# Pwr.net
KiCad netlist of a schematic drawn in Altium Designer
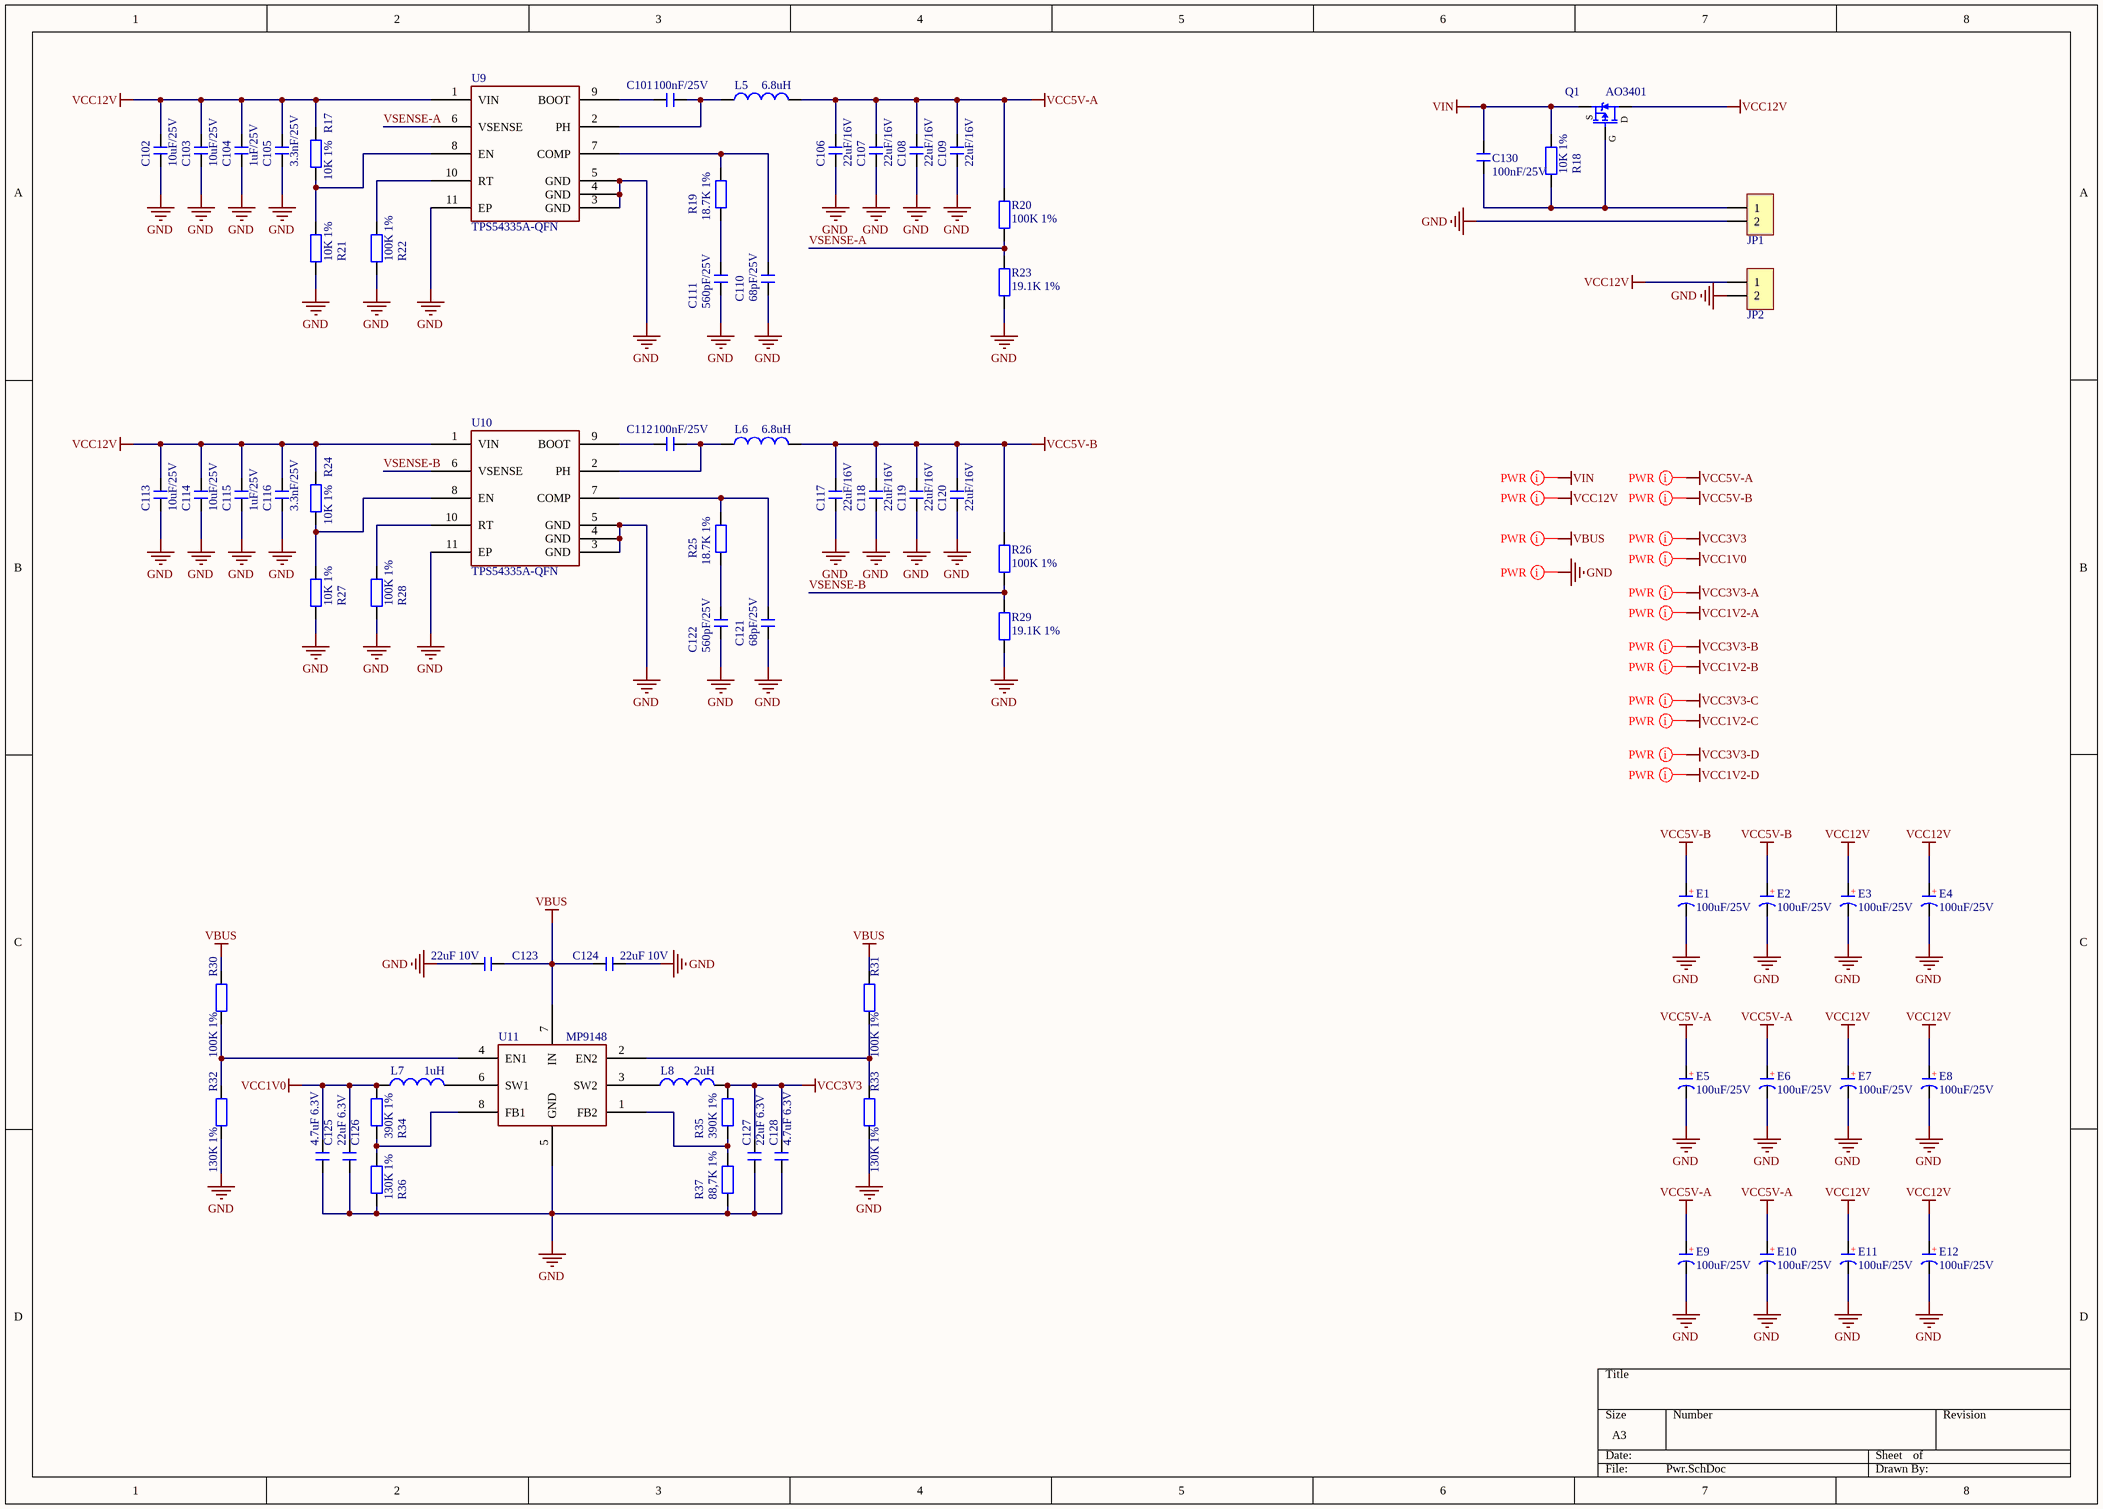
[diagram p0: Pwr.SchDoc]

(export (version "E")
  (design (tool "Eeschema 10.0.6"))
  (components
    (comp (ref "C101")
      (value "100nF/25V")
      (footprint "C0402_L")
      (description "无极性贴片电容")
      (fields (field (name "版权归属") "源创客"))
      (libsource (lib "Capacitor") (part "C"))
    )
    (comp (ref "C102")
      (value "10uF/25V")
      (footprint "C0603_L")
      (description "无极性贴片电容")
      (fields (field (name "版权归属") "源创客"))
      (libsource (lib "Capacitor") (part "C"))
    )
    (comp (ref "C103")
      (value "10uF/25V")
      (footprint "C0603_L")
      (description "无极性贴片电容")
      (fields (field (name "版权归属") "源创客"))
      (libsource (lib "Capacitor") (part "C"))
    )
    (comp (ref "C104")
      (value "1uF/25V")
      (footprint "C0603_L")
      (description "无极性贴片电容")
      (fields (field (name "版权归属") "源创客"))
      (libsource (lib "Capacitor") (part "C"))
    )
    (comp (ref "C105")
      (value "3.3nF/25V")
      (footprint "C0603_L")
      (description "无极性贴片电容")
      (fields (field (name "版权归属") "源创客"))
      (libsource (lib "Capacitor") (part "C"))
    )
    (comp (ref "C106")
      (value "22uF/16V")
      (footprint "C0603_L")
      (description "无极性贴片电容")
      (fields (field (name "版权归属") "源创客"))
      (libsource (lib "Capacitor") (part "C"))
    )
    (comp (ref "C107")
      (value "22uF/16V")
      (footprint "C0603_L")
      (description "无极性贴片电容")
      (fields (field (name "版权归属") "源创客"))
      (libsource (lib "Capacitor") (part "C"))
    )
    (comp (ref "C108")
      (value "22uF/16V")
      (footprint "C0603_L")
      (description "无极性贴片电容")
      (fields (field (name "版权归属") "源创客"))
      (libsource (lib "Capacitor") (part "C"))
    )
    (comp (ref "C109")
      (value "22uF/16V")
      (footprint "C0603_L")
      (description "无极性贴片电容")
      (fields (field (name "版权归属") "源创客"))
      (libsource (lib "Capacitor") (part "C"))
    )
    (comp (ref "C110")
      (value "68pF/25V")
      (footprint "C0402_L")
      (description "无极性贴片电容")
      (fields (field (name "版权归属") "源创客"))
      (libsource (lib "Capacitor") (part "C"))
    )
    (comp (ref "C111")
      (value "560pF/25V")
      (footprint "C0402_L")
      (description "无极性贴片电容")
      (fields (field (name "版权归属") "源创客"))
      (libsource (lib "Capacitor") (part "C"))
    )
    (comp (ref "C112")
      (value "100nF/25V")
      (footprint "C0402_L")
      (description "无极性贴片电容")
      (fields (field (name "版权归属") "源创客"))
      (libsource (lib "Capacitor") (part "C"))
    )
    (comp (ref "C113")
      (value "10uF/25V")
      (footprint "C0603_L")
      (description "无极性贴片电容")
      (fields (field (name "版权归属") "源创客"))
      (libsource (lib "Capacitor") (part "C"))
    )
    (comp (ref "C114")
      (value "10uF/25V")
      (footprint "C0603_L")
      (description "无极性贴片电容")
      (fields (field (name "版权归属") "源创客"))
      (libsource (lib "Capacitor") (part "C"))
    )
    (comp (ref "C115")
      (value "1uF/25V")
      (footprint "C0603_L")
      (description "无极性贴片电容")
      (fields (field (name "版权归属") "源创客"))
      (libsource (lib "Capacitor") (part "C"))
    )
    (comp (ref "C116")
      (value "3.3nF/25V")
      (footprint "C0603_L")
      (description "无极性贴片电容")
      (fields (field (name "版权归属") "源创客"))
      (libsource (lib "Capacitor") (part "C"))
    )
    (comp (ref "C117")
      (value "22uF/16V")
      (footprint "C0603_L")
      (description "无极性贴片电容")
      (fields (field (name "版权归属") "源创客"))
      (libsource (lib "Capacitor") (part "C"))
    )
    (comp (ref "C118")
      (value "22uF/16V")
      (footprint "C0603_L")
      (description "无极性贴片电容")
      (fields (field (name "版权归属") "源创客"))
      (libsource (lib "Capacitor") (part "C"))
    )
    (comp (ref "C119")
      (value "22uF/16V")
      (footprint "C0603_L")
      (description "无极性贴片电容")
      (fields (field (name "版权归属") "源创客"))
      (libsource (lib "Capacitor") (part "C"))
    )
    (comp (ref "C120")
      (value "22uF/16V")
      (footprint "C0603_L")
      (description "无极性贴片电容")
      (fields (field (name "版权归属") "源创客"))
      (libsource (lib "Capacitor") (part "C"))
    )
    (comp (ref "C121")
      (value "68pF/25V")
      (footprint "C0402_L")
      (description "无极性贴片电容")
      (fields (field (name "版权归属") "源创客"))
      (libsource (lib "Capacitor") (part "C"))
    )
    (comp (ref "C122")
      (value "560pF/25V")
      (footprint "C0402_L")
      (description "无极性贴片电容")
      (fields (field (name "版权归属") "源创客"))
      (libsource (lib "Capacitor") (part "C"))
    )
    (comp (ref "C123")
      (value "22uF 10V")
      (footprint "C0603_L")
      (description "无极性贴片电容")
      (fields (field (name "版权归属") "源创客"))
      (libsource (lib "Capacitor") (part "C"))
    )
    (comp (ref "C124")
      (value "22uF 10V")
      (footprint "C0603_L")
      (description "无极性贴片电容")
      (fields (field (name "版权归属") "源创客"))
      (libsource (lib "Capacitor") (part "C"))
    )
    (comp (ref "C125")
      (value "4.7uF 6.3V")
      (footprint "C0603_L")
      (description "无极性贴片电容")
      (fields (field (name "版权归属") "源创客"))
      (libsource (lib "Capacitor") (part "C"))
    )
    (comp (ref "C126")
      (value "22uF 6.3V")
      (footprint "C0603_L")
      (description "无极性贴片电容")
      (fields (field (name "版权归属") "源创客"))
      (libsource (lib "Capacitor") (part "C"))
    )
    (comp (ref "C127")
      (value "22uF 6.3V")
      (footprint "C0603_L")
      (description "无极性贴片电容")
      (fields (field (name "版权归属") "源创客"))
      (libsource (lib "Capacitor") (part "C"))
    )
    (comp (ref "C128")
      (value "4.7uF 6.3V")
      (footprint "C0603_L")
      (description "无极性贴片电容")
      (fields (field (name "版权归属") "源创客"))
      (libsource (lib "Capacitor") (part "C"))
    )
    (comp (ref "C130")
      (value "100nF/25V")
      (footprint "C0402_L")
      (description "无极性贴片电容")
      (fields (field (name "版权归属") "源创客"))
      (libsource (lib "Capacitor") (part "C"))
    )
    (comp (ref "E1")
      (value "100uF/25V")
      (footprint "CS 6*4 - B")
      (description "贴片钽电容")
      (fields (field (name "版权归属") "源创客"))
      (libsource (lib "Capacitor") (part "C-CD"))
    )
    (comp (ref "E2")
      (value "100uF/25V")
      (footprint "CS 6*4 - B")
      (description "贴片钽电容")
      (fields (field (name "版权归属") "源创客"))
      (libsource (lib "Capacitor") (part "C-CD"))
    )
    (comp (ref "E3")
      (value "100uF/25V")
      (footprint "CS 6*4 - B")
      (description "贴片钽电容")
      (fields (field (name "版权归属") "源创客"))
      (libsource (lib "Capacitor") (part "C-CD"))
    )
    (comp (ref "E4")
      (value "100uF/25V")
      (footprint "CS 6*4 - B")
      (description "贴片钽电容")
      (fields (field (name "版权归属") "源创客"))
      (libsource (lib "Capacitor") (part "C-CD"))
    )
    (comp (ref "E5")
      (value "100uF/25V")
      (footprint "CS 6*4 - B")
      (description "贴片钽电容")
      (fields (field (name "版权归属") "源创客"))
      (libsource (lib "Capacitor") (part "C-CD"))
    )
    (comp (ref "E6")
      (value "100uF/25V")
      (footprint "CS 6*4 - B")
      (description "贴片钽电容")
      (fields (field (name "版权归属") "源创客"))
      (libsource (lib "Capacitor") (part "C-CD"))
    )
    (comp (ref "E7")
      (value "100uF/25V")
      (footprint "CS 6*4 - B")
      (description "贴片钽电容")
      (fields (field (name "版权归属") "源创客"))
      (libsource (lib "Capacitor") (part "C-CD"))
    )
    (comp (ref "E8")
      (value "100uF/25V")
      (footprint "CS 6*4 - B")
      (description "贴片钽电容")
      (fields (field (name "版权归属") "源创客"))
      (libsource (lib "Capacitor") (part "C-CD"))
    )
    (comp (ref "E9")
      (value "100uF/25V")
      (footprint "CS 6*4 - B")
      (description "贴片钽电容")
      (fields (field (name "版权归属") "源创客"))
      (libsource (lib "Capacitor") (part "C-CD"))
    )
    (comp (ref "E10")
      (value "100uF/25V")
      (footprint "CS 6*4 - B")
      (description "贴片钽电容")
      (fields (field (name "版权归属") "源创客"))
      (libsource (lib "Capacitor") (part "C-CD"))
    )
    (comp (ref "E11")
      (value "100uF/25V")
      (footprint "CS 6*4 - B")
      (description "贴片钽电容")
      (fields (field (name "版权归属") "源创客"))
      (libsource (lib "Capacitor") (part "C-CD"))
    )
    (comp (ref "E12")
      (value "100uF/25V")
      (footprint "CS 6*4 - B")
      (description "贴片钽电容")
      (fields (field (name "版权归属") "源创客"))
      (libsource (lib "Capacitor") (part "C-CD"))
    )
    (comp (ref "JP1")
      (value "HDR-1X2")
      (footprint "ZH1.5-WS-2P")
      (description "2P接插件")
      (fields (field (name "版权归属") "源创客"))
      (libsource (lib "Connector-PinHeader") (part "Header 2"))
    )
    (comp (ref "JP2")
      (value "HDR-1X2")
      (footprint "XH2.54-WS-2P")
      (description "2P接插件")
      (fields (field (name "版权归属") "源创客"))
      (libsource (lib "Connector-PinHeader") (part "Header 2"))
    )
    (comp (ref "L5")
      (value "6.8uH")
      (footprint "NR4020")
      (description "小功率贴片电感")
      (fields (field (name "版权归属") "源创客"))
      (libsource (lib "Inductor") (part "L"))
    )
    (comp (ref "L6")
      (value "6.8uH")
      (footprint "NR4020")
      (description "小功率贴片电感")
      (fields (field (name "版权归属") "源创客"))
      (libsource (lib "Inductor") (part "L"))
    )
    (comp (ref "L7")
      (value "1uH")
      (footprint "NR4020")
      (description "小功率贴片电感")
      (fields (field (name "版权归属") "源创客"))
      (libsource (lib "Inductor") (part "L"))
    )
    (comp (ref "L8")
      (value "2uH")
      (footprint "NR4020")
      (description "小功率贴片电感")
      (fields (field (name "版权归属") "源创客"))
      (libsource (lib "") (part "L_1"))
    )
    (comp (ref "Q1")
      (value "AO3401")
      (footprint "DFN8-L3.0-W3.0-P0.65_EP")
      (description "P沟道 30V/4.2A")
      (fields (field (name "版权归属") "源创客"))
      (libsource (lib "MOSFET BJT IGBT") (part "AO3401"))
    )
    (comp (ref "R17")
      (value "10K 1%")
      (footprint "R0402_L")
      (description "贴片电阻")
      (fields (field (name "版权归属") "源创客"))
      (libsource (lib "Resistor") (part "R"))
    )
    (comp (ref "R18")
      (value "10K 1%")
      (footprint "R0402_L")
      (description "贴片电阻")
      (fields (field (name "版权归属") "源创客"))
      (libsource (lib "Resistor") (part "R"))
    )
    (comp (ref "R19")
      (value "18.7K 1%")
      (footprint "R0402_L")
      (description "贴片电阻")
      (fields (field (name "版权归属") "源创客"))
      (libsource (lib "Resistor") (part "R"))
    )
    (comp (ref "R20")
      (value "100K 1%")
      (footprint "R0402_L")
      (description "贴片电阻")
      (fields (field (name "版权归属") "源创客"))
      (libsource (lib "Resistor") (part "R"))
    )
    (comp (ref "R21")
      (value "10K 1%")
      (footprint "R0402_L")
      (description "贴片电阻")
      (fields (field (name "版权归属") "源创客"))
      (libsource (lib "Resistor") (part "R"))
    )
    (comp (ref "R22")
      (value "100K 1%")
      (footprint "R0402_L")
      (description "贴片电阻")
      (fields (field (name "版权归属") "源创客"))
      (libsource (lib "Resistor") (part "R"))
    )
    (comp (ref "R23")
      (value "19.1K 1%")
      (footprint "R0402_L")
      (description "贴片电阻")
      (fields (field (name "版权归属") "源创客"))
      (libsource (lib "Resistor") (part "R"))
    )
    (comp (ref "R24")
      (value "10K 1%")
      (footprint "R0402_L")
      (description "贴片电阻")
      (fields (field (name "版权归属") "源创客"))
      (libsource (lib "Resistor") (part "R"))
    )
    (comp (ref "R25")
      (value "18.7K 1%")
      (footprint "R0402_L")
      (description "贴片电阻")
      (fields (field (name "版权归属") "源创客"))
      (libsource (lib "Resistor") (part "R"))
    )
    (comp (ref "R26")
      (value "100K 1%")
      (footprint "R0402_L")
      (description "贴片电阻")
      (fields (field (name "版权归属") "源创客"))
      (libsource (lib "Resistor") (part "R"))
    )
    (comp (ref "R27")
      (value "10K 1%")
      (footprint "R0402_L")
      (description "贴片电阻")
      (fields (field (name "版权归属") "源创客"))
      (libsource (lib "Resistor") (part "R"))
    )
    (comp (ref "R28")
      (value "100K 1%")
      (footprint "R0402_L")
      (description "贴片电阻")
      (fields (field (name "版权归属") "源创客"))
      (libsource (lib "Resistor") (part "R"))
    )
    (comp (ref "R29")
      (value "19.1K 1%")
      (footprint "R0402_L")
      (description "贴片电阻")
      (fields (field (name "版权归属") "源创客"))
      (libsource (lib "Resistor") (part "R"))
    )
    (comp (ref "R30")
      (value "100K 1%")
      (footprint "R0402_L")
      (description "贴片电阻")
      (fields (field (name "版权归属") "源创客"))
      (libsource (lib "Resistor") (part "R"))
    )
    (comp (ref "R31")
      (value "100K 1%")
      (footprint "R0402_L")
      (description "贴片电阻")
      (fields (field (name "版权归属") "源创客"))
      (libsource (lib "Resistor") (part "R"))
    )
    (comp (ref "R32")
      (value "130K 1%")
      (footprint "R0402_L")
      (description "贴片电阻")
      (fields (field (name "版权归属") "源创客"))
      (libsource (lib "Resistor") (part "R"))
    )
    (comp (ref "R33")
      (value "130K 1%")
      (footprint "R0402_L")
      (description "贴片电阻")
      (fields (field (name "版权归属") "源创客"))
      (libsource (lib "Resistor") (part "R"))
    )
    (comp (ref "R34")
      (value "390K 1%")
      (footprint "R0402_L")
      (description "贴片电阻")
      (fields (field (name "版权归属") "源创客"))
      (libsource (lib "Resistor") (part "R"))
    )
    (comp (ref "R35")
      (value "390K 1%")
      (footprint "R0402_L")
      (description "贴片电阻")
      (fields (field (name "版权归属") "源创客"))
      (libsource (lib "Resistor") (part "R"))
    )
    (comp (ref "R36")
      (value "130K 1%")
      (footprint "R0402_L")
      (description "贴片电阻")
      (fields (field (name "版权归属") "源创客"))
      (libsource (lib "Resistor") (part "R"))
    )
    (comp (ref "R37")
      (value "88,7K 1%")
      (footprint "R0402_L")
      (description "贴片电阻")
      (fields (field (name "版权归属") "源创客"))
      (libsource (lib "Resistor") (part "R"))
    )
    (comp (ref "U9")
      (value "TPS54335A-QFN")
      (footprint "VSON-10_L3.0-W3.0-P0.50-TL-EP")
      (description "BUCK")
      (libsource (lib "DCDC Convert") (part "TPS54335A-QFN"))
    )
    (comp (ref "U10")
      (value "TPS54335A-QFN")
      (footprint "VSON-10_L3.0-W3.0-P0.50-TL-EP")
      (description "BUCK")
      (libsource (lib "DCDC Convert") (part "TPS54335A-QFN"))
    )
    (comp (ref "U11")
      (value "MP9148")
      (footprint "SOT23-8")
      (description "BUCK")
      (libsource (lib "DCDC Convert") (part "MP9148"))
    )
  )
  (nets
    (net (code "1") (name "/VSENSE-A") (class "Default")
      (node (ref "R20") (pin "2") (pinfunction "2_2") (pintype "passive"))
      (node (ref "R23") (pin "1") (pinfunction "1_1") (pintype "passive"))
      (node (ref "U9") (pin "6") (pinfunction "VSENSE_6") (pintype "passive"))
    )
    (net (code "2") (name "/VSENSE-B") (class "Default")
      (node (ref "R26") (pin "2") (pinfunction "2_2") (pintype "passive"))
      (node (ref "R29") (pin "1") (pinfunction "1_1") (pintype "passive"))
      (node (ref "U10") (pin "6") (pinfunction "VSENSE_6") (pintype "passive"))
    )
    (net (code "3") (name "GND") (class "Default")
      (node (ref "C102") (pin "1") (pinfunction "1_1") (pintype "passive"))
      (node (ref "C103") (pin "1") (pinfunction "1_1") (pintype "passive"))
      (node (ref "C104") (pin "1") (pinfunction "1_1") (pintype "passive"))
      (node (ref "C105") (pin "1") (pinfunction "1_1") (pintype "passive"))
      (node (ref "C106") (pin "1") (pinfunction "1_1") (pintype "passive"))
      (node (ref "C107") (pin "1") (pinfunction "1_1") (pintype "passive"))
      (node (ref "C108") (pin "1") (pinfunction "1_1") (pintype "passive"))
      (node (ref "C109") (pin "1") (pinfunction "1_1") (pintype "passive"))
      (node (ref "C110") (pin "1") (pinfunction "1_1") (pintype "passive"))
      (node (ref "C111") (pin "1") (pinfunction "1_1") (pintype "passive"))
      (node (ref "C113") (pin "1") (pinfunction "1_1") (pintype "passive"))
      (node (ref "C114") (pin "1") (pinfunction "1_1") (pintype "passive"))
      (node (ref "C115") (pin "1") (pinfunction "1_1") (pintype "passive"))
      (node (ref "C116") (pin "1") (pinfunction "1_1") (pintype "passive"))
      (node (ref "C117") (pin "1") (pinfunction "1_1") (pintype "passive"))
      (node (ref "C118") (pin "1") (pinfunction "1_1") (pintype "passive"))
      (node (ref "C119") (pin "1") (pinfunction "1_1") (pintype "passive"))
      (node (ref "C120") (pin "1") (pinfunction "1_1") (pintype "passive"))
      (node (ref "C121") (pin "1") (pinfunction "1_1") (pintype "passive"))
      (node (ref "C122") (pin "1") (pinfunction "1_1") (pintype "passive"))
      (node (ref "C123") (pin "1") (pinfunction "1_1") (pintype "passive"))
      (node (ref "C124") (pin "1") (pinfunction "1_1") (pintype "passive"))
      (node (ref "C125") (pin "1") (pinfunction "1_1") (pintype "passive"))
      (node (ref "C126") (pin "1") (pinfunction "1_1") (pintype "passive"))
      (node (ref "C127") (pin "1") (pinfunction "1_1") (pintype "passive"))
      (node (ref "C128") (pin "1") (pinfunction "1_1") (pintype "passive"))
      (node (ref "E1") (pin "2") (pinfunction "K_2") (pintype "passive"))
      (node (ref "E10") (pin "2") (pinfunction "K_2") (pintype "passive"))
      (node (ref "E11") (pin "2") (pinfunction "K_2") (pintype "passive"))
      (node (ref "E12") (pin "2") (pinfunction "K_2") (pintype "passive"))
      (node (ref "E2") (pin "2") (pinfunction "K_2") (pintype "passive"))
      (node (ref "E3") (pin "2") (pinfunction "K_2") (pintype "passive"))
      (node (ref "E4") (pin "2") (pinfunction "K_2") (pintype "passive"))
      (node (ref "E5") (pin "2") (pinfunction "K_2") (pintype "passive"))
      (node (ref "E6") (pin "2") (pinfunction "K_2") (pintype "passive"))
      (node (ref "E7") (pin "2") (pinfunction "K_2") (pintype "passive"))
      (node (ref "E8") (pin "2") (pinfunction "K_2") (pintype "passive"))
      (node (ref "E9") (pin "2") (pinfunction "K_2") (pintype "passive"))
      (node (ref "JP1") (pin "2") (pinfunction "2_2") (pintype "passive"))
      (node (ref "JP2") (pin "2") (pinfunction "2_2") (pintype "passive"))
      (node (ref "R21") (pin "2") (pinfunction "2_2") (pintype "passive"))
      (node (ref "R22") (pin "2") (pinfunction "2_2") (pintype "passive"))
      (node (ref "R23") (pin "2") (pinfunction "2_2") (pintype "passive"))
      (node (ref "R27") (pin "2") (pinfunction "2_2") (pintype "passive"))
      (node (ref "R28") (pin "2") (pinfunction "2_2") (pintype "passive"))
      (node (ref "R29") (pin "2") (pinfunction "2_2") (pintype "passive"))
      (node (ref "R32") (pin "2") (pinfunction "2_2") (pintype "passive"))
      (node (ref "R33") (pin "2") (pinfunction "2_2") (pintype "passive"))
      (node (ref "R36") (pin "2") (pinfunction "2_2") (pintype "passive"))
      (node (ref "R37") (pin "2") (pinfunction "2_2") (pintype "passive"))
      (node (ref "U10") (pin "11") (pinfunction "EP_11") (pintype "passive"))
      (node (ref "U10") (pin "3") (pinfunction "GND_3") (pintype "passive"))
      (node (ref "U10") (pin "4") (pinfunction "GND_4") (pintype "passive"))
      (node (ref "U10") (pin "5") (pinfunction "GND_5") (pintype "passive"))
      (node (ref "U11") (pin "5") (pinfunction "GND_5") (pintype "passive"))
      (node (ref "U9") (pin "11") (pinfunction "EP_11") (pintype "passive"))
      (node (ref "U9") (pin "3") (pinfunction "GND_3") (pintype "passive"))
      (node (ref "U9") (pin "4") (pinfunction "GND_4") (pintype "passive"))
      (node (ref "U9") (pin "5") (pinfunction "GND_5") (pintype "passive"))
    )
    (net (code "4") (name "Net-(C111-Pad2)") (class "Default")
      (node (ref "C111") (pin "2") (pinfunction "2_2") (pintype "passive"))
      (node (ref "R19") (pin "2") (pinfunction "2_2") (pintype "passive"))
    )
    (net (code "5") (name "Net-(C122-Pad2)") (class "Default")
      (node (ref "C122") (pin "2") (pinfunction "2_2") (pintype "passive"))
      (node (ref "R25") (pin "2") (pinfunction "2_2") (pintype "passive"))
    )
    (net (code "6") (name "Net-(Q1-G)") (class "Default")
      (node (ref "C130") (pin "2") (pinfunction "2_2") (pintype "passive"))
      (node (ref "JP1") (pin "1") (pinfunction "1_1") (pintype "passive"))
      (node (ref "Q1") (pin "1") (pinfunction "G_1") (pintype "passive"))
      (node (ref "R18") (pin "2") (pinfunction "2_2") (pintype "passive"))
    )
    (net (code "7") (name "Net-(U9-BOOT)") (class "Default")
      (node (ref "C101") (pin "2") (pinfunction "2_2") (pintype "passive"))
      (node (ref "U9") (pin "9") (pinfunction "BOOT_9") (pintype "passive"))
    )
    (net (code "8") (name "Net-(U9-COMP)") (class "Default")
      (node (ref "C110") (pin "2") (pinfunction "2_2") (pintype "passive"))
      (node (ref "R19") (pin "1") (pinfunction "1_1") (pintype "passive"))
      (node (ref "U9") (pin "7") (pinfunction "COMP_7") (pintype "passive"))
    )
    (net (code "9") (name "Net-(U9-EN)") (class "Default")
      (node (ref "R17") (pin "2") (pinfunction "2_2") (pintype "passive"))
      (node (ref "R21") (pin "1") (pinfunction "1_1") (pintype "passive"))
      (node (ref "U9") (pin "8") (pinfunction "EN_8") (pintype "passive"))
    )
    (net (code "10") (name "Net-(U9-PH)") (class "Default")
      (node (ref "C101") (pin "1") (pinfunction "1_1") (pintype "passive"))
      (node (ref "L5") (pin "1") (pinfunction "1_1") (pintype "passive"))
      (node (ref "U9") (pin "2") (pinfunction "PH_2") (pintype "passive"))
    )
    (net (code "11") (name "Net-(U9-RT)") (class "Default")
      (node (ref "R22") (pin "1") (pinfunction "1_1") (pintype "passive"))
      (node (ref "U9") (pin "10") (pinfunction "RT_10") (pintype "passive"))
    )
    (net (code "12") (name "Net-(U10-BOOT)") (class "Default")
      (node (ref "C112") (pin "2") (pinfunction "2_2") (pintype "passive"))
      (node (ref "U10") (pin "9") (pinfunction "BOOT_9") (pintype "passive"))
    )
    (net (code "13") (name "Net-(U10-COMP)") (class "Default")
      (node (ref "C121") (pin "2") (pinfunction "2_2") (pintype "passive"))
      (node (ref "R25") (pin "1") (pinfunction "1_1") (pintype "passive"))
      (node (ref "U10") (pin "7") (pinfunction "COMP_7") (pintype "passive"))
    )
    (net (code "14") (name "Net-(U10-EN)") (class "Default")
      (node (ref "R24") (pin "2") (pinfunction "2_2") (pintype "passive"))
      (node (ref "R27") (pin "1") (pinfunction "1_1") (pintype "passive"))
      (node (ref "U10") (pin "8") (pinfunction "EN_8") (pintype "passive"))
    )
    (net (code "15") (name "Net-(U10-PH)") (class "Default")
      (node (ref "C112") (pin "1") (pinfunction "1_1") (pintype "passive"))
      (node (ref "L6") (pin "1") (pinfunction "1_1") (pintype "passive"))
      (node (ref "U10") (pin "2") (pinfunction "PH_2") (pintype "passive"))
    )
    (net (code "16") (name "Net-(U10-RT)") (class "Default")
      (node (ref "R28") (pin "1") (pinfunction "1_1") (pintype "passive"))
      (node (ref "U10") (pin "10") (pinfunction "RT_10") (pintype "passive"))
    )
    (net (code "17") (name "Net-(U11-EN1)") (class "Default")
      (node (ref "R30") (pin "2") (pinfunction "2_2") (pintype "passive"))
      (node (ref "R32") (pin "1") (pinfunction "1_1") (pintype "passive"))
      (node (ref "U11") (pin "4") (pinfunction "EN1_4") (pintype "passive"))
    )
    (net (code "18") (name "Net-(U11-EN2)") (class "Default")
      (node (ref "R31") (pin "2") (pinfunction "2_2") (pintype "passive"))
      (node (ref "R33") (pin "1") (pinfunction "1_1") (pintype "passive"))
      (node (ref "U11") (pin "2") (pinfunction "EN2_2") (pintype "passive"))
    )
    (net (code "19") (name "Net-(U11-FB1)") (class "Default")
      (node (ref "R34") (pin "2") (pinfunction "2_2") (pintype "passive"))
      (node (ref "R36") (pin "1") (pinfunction "1_1") (pintype "passive"))
      (node (ref "U11") (pin "8") (pinfunction "FB1_8") (pintype "passive"))
    )
    (net (code "20") (name "Net-(U11-FB2)") (class "Default")
      (node (ref "R35") (pin "2") (pinfunction "2_2") (pintype "passive"))
      (node (ref "R37") (pin "1") (pinfunction "1_1") (pintype "passive"))
      (node (ref "U11") (pin "1") (pinfunction "FB2_1") (pintype "passive"))
    )
    (net (code "21") (name "Net-(U11-SW1)") (class "Default")
      (node (ref "L7") (pin "2") (pinfunction "2_2") (pintype "passive"))
      (node (ref "U11") (pin "6") (pinfunction "SW1_6") (pintype "passive"))
    )
    (net (code "22") (name "Net-(U11-SW2)") (class "Default")
      (node (ref "L8") (pin "2") (pinfunction "2_2") (pintype "passive"))
      (node (ref "U11") (pin "3") (pinfunction "SW2_3") (pintype "passive"))
    )
    (net (code "23") (name "VBUS") (class "Default")
      (node (ref "C123") (pin "2") (pinfunction "2_2") (pintype "passive"))
      (node (ref "C124") (pin "2") (pinfunction "2_2") (pintype "passive"))
      (node (ref "R30") (pin "1") (pinfunction "1_1") (pintype "passive"))
      (node (ref "R31") (pin "1") (pinfunction "1_1") (pintype "passive"))
      (node (ref "U11") (pin "7") (pinfunction "IN_7") (pintype "passive"))
    )
    (net (code "24") (name "VCC1V0") (class "Default")
      (node (ref "C125") (pin "2") (pinfunction "2_2") (pintype "passive"))
      (node (ref "C126") (pin "2") (pinfunction "2_2") (pintype "passive"))
      (node (ref "L7") (pin "1") (pinfunction "1_1") (pintype "passive"))
      (node (ref "R34") (pin "1") (pinfunction "1_1") (pintype "passive"))
    )
    (net (code "29") (name "VCC3V3") (class "Default")
      (node (ref "C127") (pin "2") (pinfunction "2_2") (pintype "passive"))
      (node (ref "C128") (pin "2") (pinfunction "2_2") (pintype "passive"))
      (node (ref "L8") (pin "1") (pinfunction "1_1") (pintype "passive"))
      (node (ref "R35") (pin "1") (pinfunction "1_1") (pintype "passive"))
    )
    (net (code "34") (name "VCC5V-A") (class "Default")
      (node (ref "C106") (pin "2") (pinfunction "2_2") (pintype "passive"))
      (node (ref "C107") (pin "2") (pinfunction "2_2") (pintype "passive"))
      (node (ref "C108") (pin "2") (pinfunction "2_2") (pintype "passive"))
      (node (ref "C109") (pin "2") (pinfunction "2_2") (pintype "passive"))
      (node (ref "E10") (pin "1") (pinfunction "A_1") (pintype "passive"))
      (node (ref "E5") (pin "1") (pinfunction "A_1") (pintype "passive"))
      (node (ref "E6") (pin "1") (pinfunction "A_1") (pintype "passive"))
      (node (ref "E9") (pin "1") (pinfunction "A_1") (pintype "passive"))
      (node (ref "L5") (pin "2") (pinfunction "2_2") (pintype "passive"))
      (node (ref "R20") (pin "1") (pinfunction "1_1") (pintype "passive"))
    )
    (net (code "35") (name "VCC5V-B") (class "Default")
      (node (ref "C117") (pin "2") (pinfunction "2_2") (pintype "passive"))
      (node (ref "C118") (pin "2") (pinfunction "2_2") (pintype "passive"))
      (node (ref "C119") (pin "2") (pinfunction "2_2") (pintype "passive"))
      (node (ref "C120") (pin "2") (pinfunction "2_2") (pintype "passive"))
      (node (ref "E1") (pin "1") (pinfunction "A_1") (pintype "passive"))
      (node (ref "E2") (pin "1") (pinfunction "A_1") (pintype "passive"))
      (node (ref "L6") (pin "2") (pinfunction "2_2") (pintype "passive"))
      (node (ref "R26") (pin "1") (pinfunction "1_1") (pintype "passive"))
    )
    (net (code "36") (name "VCC12V") (class "Default")
      (node (ref "C102") (pin "2") (pinfunction "2_2") (pintype "passive"))
      (node (ref "C103") (pin "2") (pinfunction "2_2") (pintype "passive"))
      (node (ref "C104") (pin "2") (pinfunction "2_2") (pintype "passive"))
      (node (ref "C105") (pin "2") (pinfunction "2_2") (pintype "passive"))
      (node (ref "C113") (pin "2") (pinfunction "2_2") (pintype "passive"))
      (node (ref "C114") (pin "2") (pinfunction "2_2") (pintype "passive"))
      (node (ref "C115") (pin "2") (pinfunction "2_2") (pintype "passive"))
      (node (ref "C116") (pin "2") (pinfunction "2_2") (pintype "passive"))
      (node (ref "E11") (pin "1") (pinfunction "A_1") (pintype "passive"))
      (node (ref "E12") (pin "1") (pinfunction "A_1") (pintype "passive"))
      (node (ref "E3") (pin "1") (pinfunction "A_1") (pintype "passive"))
      (node (ref "E4") (pin "1") (pinfunction "A_1") (pintype "passive"))
      (node (ref "E7") (pin "1") (pinfunction "A_1") (pintype "passive"))
      (node (ref "E8") (pin "1") (pinfunction "A_1") (pintype "passive"))
      (node (ref "JP2") (pin "1") (pinfunction "1_1") (pintype "passive"))
      (node (ref "Q1") (pin "3") (pinfunction "D_3") (pintype "passive"))
      (node (ref "R17") (pin "1") (pinfunction "1_1") (pintype "passive"))
      (node (ref "R24") (pin "1") (pinfunction "1_1") (pintype "passive"))
      (node (ref "U10") (pin "1") (pinfunction "VIN_1") (pintype "passive"))
      (node (ref "U9") (pin "1") (pinfunction "VIN_1") (pintype "passive"))
    )
    (net (code "37") (name "VIN") (class "Default")
      (node (ref "C130") (pin "1") (pinfunction "1_1") (pintype "passive"))
      (node (ref "Q1") (pin "2") (pinfunction "S_2") (pintype "passive"))
      (node (ref "R18") (pin "1") (pinfunction "1_1") (pintype "passive"))
    )
  )
)
